# usb-microphone-v0001.net
KiCad netlist of a schematic drawn in EAGLE
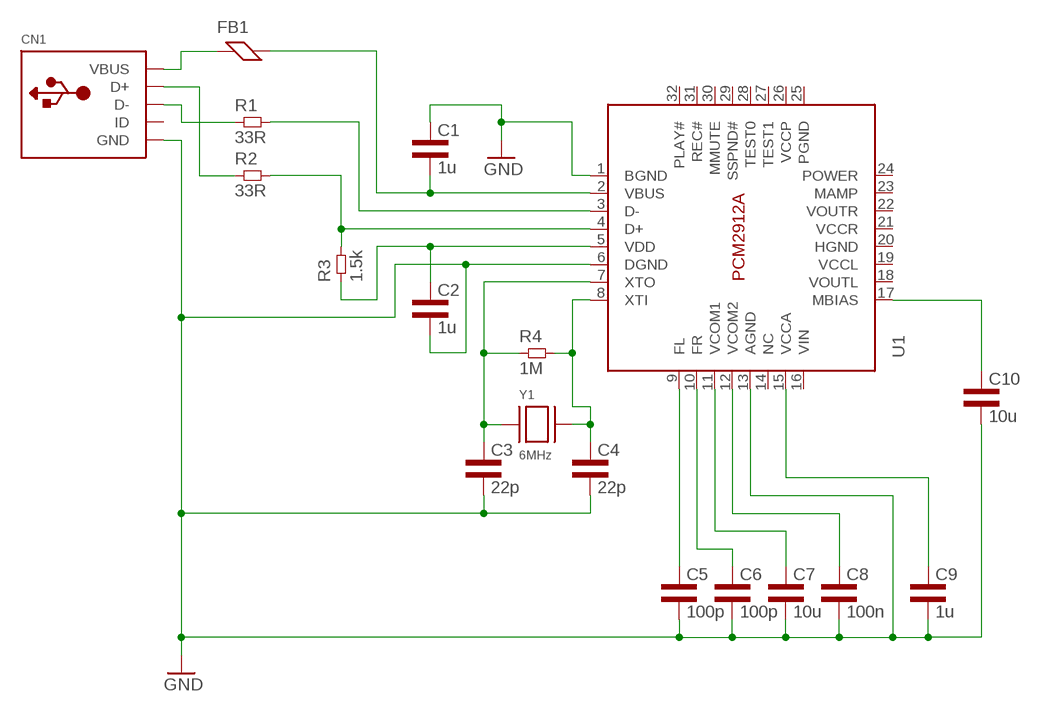
[diagram p0: schematic, sheet 1]

(export (version "E")
  (design (tool "Eeschema 10.0.6"))
  (components
    (comp (ref "C1")
      (value "1u")
      (footprint "eagle-import:0603L3")
      (libsource (lib "eagle-import") (part "CAP0603L3"))
    )
    (comp (ref "C2")
      (value "1u")
      (footprint "eagle-import:0603L3")
      (libsource (lib "eagle-import") (part "CAP0603L3"))
    )
    (comp (ref "C3")
      (value "22p")
      (footprint "eagle-import:0603L3")
      (libsource (lib "eagle-import") (part "CAP0603L3"))
    )
    (comp (ref "C4")
      (value "22p")
      (footprint "eagle-import:0603L3")
      (libsource (lib "eagle-import") (part "CAP0603L3"))
    )
    (comp (ref "C5")
      (value "100p")
      (footprint "eagle-import:0603L3")
      (libsource (lib "eagle-import") (part "CAP0603L3"))
    )
    (comp (ref "C6")
      (value "100p")
      (footprint "eagle-import:0603L3")
      (libsource (lib "eagle-import") (part "CAP0603L3"))
    )
    (comp (ref "C7")
      (value "10u")
      (footprint "eagle-import:0805L3")
      (libsource (lib "eagle-import") (part "CAP0805L3"))
    )
    (comp (ref "C8")
      (value "100n")
      (footprint "eagle-import:0603L3")
      (libsource (lib "eagle-import") (part "CAP0603L3"))
    )
    (comp (ref "C9")
      (value "1u")
      (footprint "eagle-import:0603L3")
      (libsource (lib "eagle-import") (part "CAP0603L3"))
    )
    (comp (ref "C10")
      (value "10u")
      (footprint "eagle-import:0805L3")
      (libsource (lib "eagle-import") (part "CAP0805L3"))
    )
    (comp (ref "CN1")
      (value "ADAFRUIT_USBMINIB")
      (footprint "eagle-import:ADAFRUIT_USB-MINIB")
      (libsource (lib "eagle-import") (part "ADAFRUIT_USBMINIB"))
    )
    (comp (ref "FB1")
      (value "FERRITE0805L3")
      (footprint "eagle-import:0805L3")
      (libsource (lib "eagle-import") (part "FERRITE0805L3"))
    )
    (comp (ref "R1")
      (value "33R")
      (footprint "eagle-import:0603L3")
      (libsource (lib "eagle-import") (part "RES0603L3"))
    )
    (comp (ref "R2")
      (value "33R")
      (footprint "eagle-import:0603L3")
      (libsource (lib "eagle-import") (part "RES0603L3"))
    )
    (comp (ref "R3")
      (value "1.5k")
      (footprint "eagle-import:0603L3")
      (libsource (lib "eagle-import") (part "RES0603L3"))
    )
    (comp (ref "R4")
      (value "1M")
      (footprint "eagle-import:0603L3")
      (libsource (lib "eagle-import") (part "RES0603L3"))
    )
    (comp (ref "U1")
      (value "PCM2912A")
      (footprint "eagle-import:S-PQFP-N32")
      (libsource (lib "eagle-import") (part "PCM2912A"))
    )
    (comp (ref "Y1")
      (value "6MHz")
      (footprint "eagle-import:SMD-11.7X4.8")
      (libsource (lib "eagle-import") (part "CRYSTALSMD-11.7X4.8"))
    )
  )
  (nets
    (net (code "1") (name "GND") (class "Default")
      (node (ref "C1") (pin "P$1") (pinfunction "1_P$1") (pintype "bidirectional"))
      (node (ref "C10") (pin "2") (pinfunction "2_2") (pintype "bidirectional"))
      (node (ref "C2") (pin "P$2") (pinfunction "2_P$2") (pintype "bidirectional"))
      (node (ref "C3") (pin "P$2") (pinfunction "2_P$2") (pintype "bidirectional"))
      (node (ref "C4") (pin "P$2") (pinfunction "2_P$2") (pintype "bidirectional"))
      (node (ref "C5") (pin "P$2") (pinfunction "2_P$2") (pintype "bidirectional"))
      (node (ref "C6") (pin "P$2") (pinfunction "2_P$2") (pintype "bidirectional"))
      (node (ref "C7") (pin "2") (pinfunction "2_2") (pintype "bidirectional"))
      (node (ref "C8") (pin "P$2") (pinfunction "2_P$2") (pintype "bidirectional"))
      (node (ref "C9") (pin "P$2") (pinfunction "2_P$2") (pintype "bidirectional"))
      (node (ref "CN1") (pin "GND") (pinfunction "GND_GND") (pintype "power_in"))
      (node (ref "U1") (pin "1") (pinfunction "BGND_1") (pintype "bidirectional"))
      (node (ref "U1") (pin "13") (pinfunction "AGND_13") (pintype "bidirectional"))
      (node (ref "U1") (pin "6") (pinfunction "DGND_6") (pintype "bidirectional"))
    )
    (net (code "2") (name "Net-(C1-2)") (class "Default")
      (node (ref "C1") (pin "P$2") (pinfunction "2_P$2") (pintype "bidirectional"))
      (node (ref "FB1") (pin "2") (pinfunction "2_2") (pintype "bidirectional"))
      (node (ref "U1") (pin "2") (pinfunction "VBUS_2") (pintype "bidirectional"))
    )
    (net (code "3") (name "Net-(C2-1)") (class "Default")
      (node (ref "C2") (pin "P$1") (pinfunction "1_P$1") (pintype "bidirectional"))
      (node (ref "R3") (pin "P$1") (pinfunction "1_P$1") (pintype "bidirectional"))
      (node (ref "U1") (pin "5") (pinfunction "VDD_5") (pintype "bidirectional"))
    )
    (net (code "4") (name "Net-(C3-1)") (class "Default")
      (node (ref "C3") (pin "P$1") (pinfunction "1_P$1") (pintype "bidirectional"))
      (node (ref "R4") (pin "P$1") (pinfunction "1_P$1") (pintype "bidirectional"))
      (node (ref "U1") (pin "7") (pinfunction "XTO_7") (pintype "bidirectional"))
      (node (ref "Y1") (pin "1") (pinfunction "P$1_1") (pintype "bidirectional"))
    )
    (net (code "5") (name "Net-(C4-1)") (class "Default")
      (node (ref "C4") (pin "P$1") (pinfunction "1_P$1") (pintype "bidirectional"))
      (node (ref "R4") (pin "P$2") (pinfunction "2_P$2") (pintype "bidirectional"))
      (node (ref "U1") (pin "8") (pinfunction "XTI_8") (pintype "bidirectional"))
      (node (ref "Y1") (pin "4") (pinfunction "P$2_4") (pintype "bidirectional"))
    )
    (net (code "6") (name "Net-(C5-1)") (class "Default")
      (node (ref "C5") (pin "P$1") (pinfunction "1_P$1") (pintype "bidirectional"))
      (node (ref "U1") (pin "9") (pinfunction "FL_9") (pintype "bidirectional"))
    )
    (net (code "7") (name "Net-(C6-1)") (class "Default")
      (node (ref "C6") (pin "P$1") (pinfunction "1_P$1") (pintype "bidirectional"))
      (node (ref "U1") (pin "10") (pinfunction "FR_10") (pintype "bidirectional"))
    )
    (net (code "8") (name "Net-(C8-1)") (class "Default")
      (node (ref "C8") (pin "P$1") (pinfunction "1_P$1") (pintype "bidirectional"))
      (node (ref "U1") (pin "12") (pinfunction "VCOM2_12") (pintype "bidirectional"))
    )
    (net (code "9") (name "Net-(C9-1)") (class "Default")
      (node (ref "C9") (pin "P$1") (pinfunction "1_P$1") (pintype "bidirectional"))
      (node (ref "U1") (pin "15") (pinfunction "VCCA_15") (pintype "bidirectional"))
    )
    (net (code "10") (name "Net-(CN1-PadVBUS)") (class "Default")
      (node (ref "CN1") (pin "VBUS") (pinfunction "VBUS_VBUS") (pintype "power_in"))
      (node (ref "FB1") (pin "1") (pinfunction "1_1") (pintype "bidirectional"))
    )
    (net (code "11") (name "Net-(R1-1)") (class "Default")
      (node (ref "CN1") (pin "D-") (pinfunction "D-_D-") (pintype "bidirectional"))
      (node (ref "R1") (pin "P$1") (pinfunction "1_P$1") (pintype "bidirectional"))
    )
    (net (code "12") (name "Net-(R1-2)") (class "Default")
      (node (ref "R1") (pin "P$2") (pinfunction "2_P$2") (pintype "bidirectional"))
      (node (ref "U1") (pin "3") (pinfunction "D-_3") (pintype "bidirectional"))
    )
    (net (code "13") (name "Net-(R2-1)") (class "Default")
      (node (ref "CN1") (pin "D+") (pinfunction "D+_D+") (pintype "bidirectional"))
      (node (ref "R2") (pin "P$1") (pinfunction "1_P$1") (pintype "bidirectional"))
    )
    (net (code "14") (name "Net-(R2-2)") (class "Default")
      (node (ref "R2") (pin "P$2") (pinfunction "2_P$2") (pintype "bidirectional"))
      (node (ref "R3") (pin "P$2") (pinfunction "2_P$2") (pintype "bidirectional"))
      (node (ref "U1") (pin "4") (pinfunction "D+_4") (pintype "bidirectional"))
    )
    (net (code "15") (name "Net-(U1-MBIAS)") (class "Default")
      (node (ref "C10") (pin "1") (pinfunction "1_1") (pintype "bidirectional"))
      (node (ref "U1") (pin "17") (pinfunction "MBIAS_17") (pintype "bidirectional"))
    )
    (net (code "16") (name "Net-(U1-VCOM1)") (class "Default")
      (node (ref "C7") (pin "1") (pinfunction "1_1") (pintype "bidirectional"))
      (node (ref "U1") (pin "11") (pinfunction "VCOM1_11") (pintype "bidirectional"))
    )
    (net (code "17") (name "unconnected-(CN1-PadID)") (class "Default")
      (node (ref "CN1") (pin "ID") (pinfunction "ID_ID") (pintype "bidirectional"))
    )
    (net (code "18") (name "unconnected-(U1-HGND-Pad20)") (class "Default")
      (node (ref "U1") (pin "20") (pinfunction "HGND_20") (pintype "bidirectional"))
    )
    (net (code "19") (name "unconnected-(U1-MAMP-Pad23)") (class "Default")
      (node (ref "U1") (pin "23") (pinfunction "MAMP_23") (pintype "bidirectional"))
    )
    (net (code "20") (name "unconnected-(U1-MMUTE-Pad30)") (class "Default")
      (node (ref "U1") (pin "30") (pinfunction "MMUTE_30") (pintype "bidirectional"))
    )
    (net (code "21") (name "unconnected-(U1-NC-Pad14)") (class "Default")
      (node (ref "U1") (pin "14") (pinfunction "NC_14") (pintype "bidirectional"))
    )
    (net (code "22") (name "unconnected-(U1-PGND-Pad25)") (class "Default")
      (node (ref "U1") (pin "25") (pinfunction "PGND_25") (pintype "bidirectional"))
    )
    (net (code "23") (name "unconnected-(U1-PLAY#-Pad32)") (class "Default")
      (node (ref "U1") (pin "32") (pinfunction "PLAY#_32") (pintype "bidirectional"))
    )
    (net (code "24") (name "unconnected-(U1-POWER-Pad24)") (class "Default")
      (node (ref "U1") (pin "24") (pinfunction "POWER_24") (pintype "bidirectional"))
    )
    (net (code "25") (name "unconnected-(U1-REC#-Pad31)") (class "Default")
      (node (ref "U1") (pin "31") (pinfunction "REC#_31") (pintype "bidirectional"))
    )
    (net (code "26") (name "unconnected-(U1-SSPND#-Pad29)") (class "Default")
      (node (ref "U1") (pin "29") (pinfunction "SSPND#_29") (pintype "bidirectional"))
    )
    (net (code "27") (name "unconnected-(U1-TEST0-Pad28)") (class "Default")
      (node (ref "U1") (pin "28") (pinfunction "TEST0_28") (pintype "bidirectional"))
    )
    (net (code "28") (name "unconnected-(U1-TEST1-Pad27)") (class "Default")
      (node (ref "U1") (pin "27") (pinfunction "TEST1_27") (pintype "bidirectional"))
    )
    (net (code "29") (name "unconnected-(U1-VCCL-Pad19)") (class "Default")
      (node (ref "U1") (pin "19") (pinfunction "VCCL_19") (pintype "bidirectional"))
    )
    (net (code "30") (name "unconnected-(U1-VCCP-Pad26)") (class "Default")
      (node (ref "U1") (pin "26") (pinfunction "VCCP_26") (pintype "bidirectional"))
    )
    (net (code "31") (name "unconnected-(U1-VCCR-Pad21)") (class "Default")
      (node (ref "U1") (pin "21") (pinfunction "VCCR_21") (pintype "bidirectional"))
    )
    (net (code "32") (name "unconnected-(U1-VIN-Pad16)") (class "Default")
      (node (ref "U1") (pin "16") (pinfunction "VIN_16") (pintype "bidirectional"))
    )
    (net (code "33") (name "unconnected-(U1-VOUTL-Pad18)") (class "Default")
      (node (ref "U1") (pin "18") (pinfunction "VOUTL_18") (pintype "bidirectional"))
    )
    (net (code "34") (name "unconnected-(U1-VOUTR-Pad22)") (class "Default")
      (node (ref "U1") (pin "22") (pinfunction "VOUTR_22") (pintype "bidirectional"))
    )
  )
)
